# MCU.net
KiCad netlist of a schematic drawn in Altium Designer
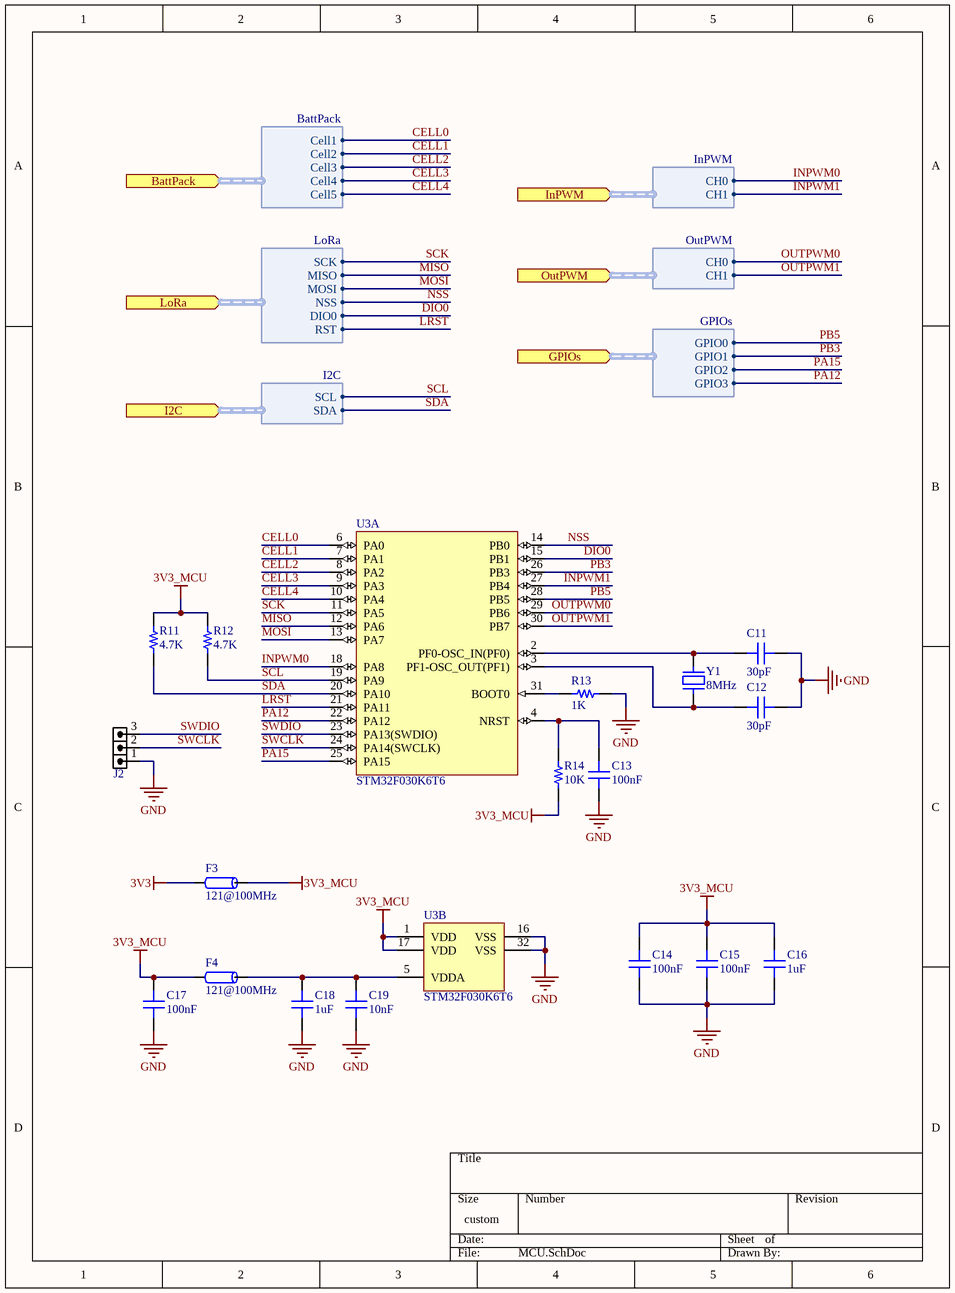
[diagram p0: MCU.SchDoc]

(export (version "E")
  (design (tool "Eeschema 10.0.6"))
  (components
    (comp (ref "C11")
      (value "30pF")
      (footprint "CAP 0603_1608")
      (description "SMT Capacitor")
      (libsource (lib "Capacitor") (part "Cap 0603"))
    )
    (comp (ref "C12")
      (value "30pF")
      (footprint "CAP 0603_1608")
      (description "SMT Capacitor")
      (libsource (lib "Capacitor") (part "Cap 0603"))
    )
    (comp (ref "C13")
      (value "100nF")
      (footprint "CAP 0603_1608")
      (description "SMT Capacitor")
      (libsource (lib "Capacitor") (part "Cap 0603"))
    )
    (comp (ref "C14")
      (value "100nF")
      (footprint "CAP 0603_1608")
      (description "SMT Capacitor")
      (libsource (lib "Capacitor") (part "Cap 0603"))
    )
    (comp (ref "C15")
      (value "100nF")
      (footprint "CAP 0603_1608")
      (description "SMT Capacitor")
      (libsource (lib "Capacitor") (part "Cap 0603"))
    )
    (comp (ref "C16")
      (value "1uF")
      (footprint "CAP 0603_1608")
      (description "SMT Capacitor")
      (libsource (lib "Capacitor") (part "Cap 0603"))
    )
    (comp (ref "C17")
      (value "100nF")
      (footprint "CAP 0603_1608")
      (description "SMT Capacitor")
      (libsource (lib "Capacitor") (part "Cap 0603"))
    )
    (comp (ref "C18")
      (value "1uF")
      (footprint "CAP 0603_1608")
      (description "SMT Capacitor")
      (libsource (lib "Capacitor") (part "Cap 0603"))
    )
    (comp (ref "C19")
      (value "10nF")
      (footprint "CAP 0603_1608")
      (description "SMT Capacitor")
      (libsource (lib "Capacitor") (part "Cap 0603"))
    )
    (comp (ref "F3")
      (value "121@100MHz")
      (footprint "Ferrite-0805")
      (description "Ferrite Bead")
      (libsource (lib "Salman_lib") (part "Ferrite Bead"))
    )
    (comp (ref "F4")
      (value "121@100MHz")
      (footprint "Ferrite-0805")
      (description "Ferrite Bead")
      (libsource (lib "Salman_lib") (part "Ferrite Bead"))
    )
    (comp (ref "J2")
      (value "HDRM3")
      (footprint "HDR_M_1X3")
      (description "CONN, HEADER, Male, pitch: 2.54mm, 3POS")
      (libsource (lib "Conn Header") (part "HDR_M_1X3"))
    )
    (comp (ref "R11")
      (value "4.7K")
      (footprint "RES 0603_1608")
      (description "SMT Resistor")
      (libsource (lib "Resistor") (part "Res 0603"))
    )
    (comp (ref "R12")
      (value "4.7K")
      (footprint "RES 0603_1608")
      (description "SMT Resistor")
      (libsource (lib "Resistor") (part "Res 0603"))
    )
    (comp (ref "R13")
      (value "1K")
      (footprint "RES 0603_1608")
      (description "SMT Resistor")
      (libsource (lib "Resistor") (part "Res 0603"))
    )
    (comp (ref "R14")
      (value "10K")
      (footprint "RES 0603_1608")
      (description "SMT Resistor")
      (libsource (lib "Resistor") (part "Res 0603"))
    )
    (comp (ref "U3")
      (value "STM32F030K6T6")
      (footprint "LQFP-32 7X7MM P0.8MM")
      (libsource (lib "Mcu") (part "STM32F030K6T6"))
    )
    (comp (ref "Y1")
      (value "8MHz")
      (footprint "HC-49S SMD")
      (description "SMT Crystal")
      (fields (field (name "PARTNUMBER") "ABLS-8.000MHZ-K4T"))
      (libsource (lib "Xtal") (part "Crystal HC-49S SMD 8MHz"))
    )
  )
  (nets
    (net (code "7") (name "/CELL0") (class "Default")
      (node (ref "U3") (pin "6") (pinfunction "PA0_6") (pintype "bidirectional"))
    )
    (net (code "8") (name "/CELL1") (class "Default")
      (node (ref "U3") (pin "7") (pinfunction "PA1_7") (pintype "bidirectional"))
    )
    (net (code "9") (name "/CELL2") (class "Default")
      (node (ref "U3") (pin "8") (pinfunction "PA2_8") (pintype "bidirectional"))
    )
    (net (code "10") (name "/CELL3") (class "Default")
      (node (ref "U3") (pin "9") (pinfunction "PA3_9") (pintype "bidirectional"))
    )
    (net (code "11") (name "/CELL4") (class "Default")
      (node (ref "U3") (pin "10") (pinfunction "PA4_10") (pintype "bidirectional"))
    )
    (net (code "12") (name "/DIO0") (class "Default")
      (node (ref "U3") (pin "15") (pinfunction "PB1_15") (pintype "bidirectional"))
    )
    (net (code "13") (name "/INPWM0") (class "Default")
      (node (ref "U3") (pin "18") (pinfunction "PA8_18") (pintype "bidirectional"))
    )
    (net (code "14") (name "/INPWM1") (class "Default")
      (node (ref "U3") (pin "27") (pinfunction "PB4_27") (pintype "bidirectional"))
    )
    (net (code "15") (name "/LRST") (class "Default")
      (node (ref "U3") (pin "21") (pinfunction "PA11_21") (pintype "bidirectional"))
    )
    (net (code "16") (name "/MISO") (class "Default")
      (node (ref "U3") (pin "12") (pinfunction "PA6_12") (pintype "bidirectional"))
    )
    (net (code "17") (name "/MOSI") (class "Default")
      (node (ref "U3") (pin "13") (pinfunction "PA7_13") (pintype "bidirectional"))
    )
    (net (code "18") (name "/NSS") (class "Default")
      (node (ref "U3") (pin "14") (pinfunction "PB0_14") (pintype "bidirectional"))
    )
    (net (code "19") (name "/OUTPWM0") (class "Default")
      (node (ref "U3") (pin "29") (pinfunction "PB6_29") (pintype "bidirectional"))
    )
    (net (code "20") (name "/OUTPWM1") (class "Default")
      (node (ref "U3") (pin "30") (pinfunction "PB7_30") (pintype "bidirectional"))
    )
    (net (code "21") (name "/PA12") (class "Default")
      (node (ref "U3") (pin "22") (pinfunction "PA12_22") (pintype "bidirectional"))
    )
    (net (code "22") (name "/PA15") (class "Default")
      (node (ref "U3") (pin "25") (pinfunction "PA15_25") (pintype "bidirectional"))
    )
    (net (code "23") (name "/PB3") (class "Default")
      (node (ref "U3") (pin "26") (pinfunction "PB3_26") (pintype "bidirectional"))
    )
    (net (code "24") (name "/PB5") (class "Default")
      (node (ref "U3") (pin "28") (pinfunction "PB5_28") (pintype "bidirectional"))
    )
    (net (code "25") (name "/SCK") (class "Default")
      (node (ref "U3") (pin "11") (pinfunction "PA5_11") (pintype "bidirectional"))
    )
    (net (code "26") (name "/SCL") (class "Default")
      (node (ref "R12") (pin "1") (pinfunction "1_1") (pintype "passive"))
      (node (ref "U3") (pin "19") (pinfunction "PA9_19") (pintype "bidirectional"))
    )
    (net (code "27") (name "/SDA") (class "Default")
      (node (ref "R11") (pin "1") (pinfunction "1_1") (pintype "passive"))
      (node (ref "U3") (pin "20") (pinfunction "PA10_20") (pintype "bidirectional"))
    )
    (net (code "28") (name "/SWCLK") (class "Default")
      (node (ref "J2") (pin "2") (pinfunction "2_2") (pintype "passive"))
      (node (ref "U3") (pin "24") (pinfunction "PA14(SWCLK)_24") (pintype "bidirectional"))
    )
    (net (code "29") (name "/SWDIO") (class "Default")
      (node (ref "J2") (pin "3") (pinfunction "3_3") (pintype "passive"))
      (node (ref "U3") (pin "23") (pinfunction "PA13(SWDIO)_23") (pintype "bidirectional"))
    )
    (net (code "36") (name "3V3") (class "Default")
      (node (ref "F3") (pin "1") (pinfunction "67_1") (pintype "passive"))
    )
    (net (code "37") (name "3V3_MCU") (class "Default")
      (node (ref "C14") (pin "2") (pinfunction "2_2") (pintype "passive"))
      (node (ref "C15") (pin "2") (pinfunction "2_2") (pintype "passive"))
      (node (ref "C16") (pin "2") (pinfunction "2_2") (pintype "passive"))
      (node (ref "C17") (pin "2") (pinfunction "2_2") (pintype "passive"))
      (node (ref "F3") (pin "2") (pinfunction "66_2") (pintype "passive"))
      (node (ref "F4") (pin "1") (pinfunction "67_1") (pintype "passive"))
      (node (ref "R11") (pin "2") (pinfunction "2_2") (pintype "passive"))
      (node (ref "R12") (pin "2") (pinfunction "2_2") (pintype "passive"))
      (node (ref "R14") (pin "1") (pinfunction "1_1") (pintype "passive"))
      (node (ref "U3") (pin "1") (pinfunction "VDD_1") (pintype "power_in"))
      (node (ref "U3") (pin "17") (pinfunction "VDD_17") (pintype "power_in"))
    )
    (net (code "38") (name "GND") (class "Default")
      (node (ref "C11") (pin "2") (pinfunction "2_2") (pintype "passive"))
      (node (ref "C12") (pin "2") (pinfunction "2_2") (pintype "passive"))
      (node (ref "C13") (pin "1") (pinfunction "1_1") (pintype "passive"))
      (node (ref "C14") (pin "1") (pinfunction "1_1") (pintype "passive"))
      (node (ref "C15") (pin "1") (pinfunction "1_1") (pintype "passive"))
      (node (ref "C16") (pin "1") (pinfunction "1_1") (pintype "passive"))
      (node (ref "C17") (pin "1") (pinfunction "1_1") (pintype "passive"))
      (node (ref "C18") (pin "1") (pinfunction "1_1") (pintype "passive"))
      (node (ref "C19") (pin "1") (pinfunction "1_1") (pintype "passive"))
      (node (ref "J2") (pin "1") (pinfunction "1_1") (pintype "passive"))
      (node (ref "R13") (pin "2") (pinfunction "2_2") (pintype "passive"))
      (node (ref "U3") (pin "16") (pinfunction "VSS_16") (pintype "power_in"))
      (node (ref "U3") (pin "32") (pinfunction "VSS_32") (pintype "power_in"))
    )
    (net (code "39") (name "Net-(F4-66)") (class "Default")
      (node (ref "C18") (pin "2") (pinfunction "2_2") (pintype "passive"))
      (node (ref "C19") (pin "2") (pinfunction "2_2") (pintype "passive"))
      (node (ref "F4") (pin "2") (pinfunction "66_2") (pintype "passive"))
      (node (ref "U3") (pin "5") (pinfunction "VDDA_5") (pintype "power_in"))
    )
    (net (code "40") (name "Net-(U3A-BOOT0)") (class "Default")
      (node (ref "R13") (pin "1") (pinfunction "1_1") (pintype "passive"))
      (node (ref "U3") (pin "31") (pinfunction "BOOT0_31") (pintype "input"))
    )
    (net (code "41") (name "Net-(U3A-NRST)") (class "Default")
      (node (ref "C13") (pin "2") (pinfunction "2_2") (pintype "passive"))
      (node (ref "R14") (pin "2") (pinfunction "2_2") (pintype "passive"))
      (node (ref "U3") (pin "4") (pinfunction "NRST_4") (pintype "bidirectional"))
    )
    (net (code "42") (name "Net-(U3A-PF0-OSC_IN(PF0))") (class "Default")
      (node (ref "C11") (pin "1") (pinfunction "1_1") (pintype "passive"))
      (node (ref "U3") (pin "2") (pinfunction "PF0-OSC_IN(PF0)_2") (pintype "bidirectional"))
      (node (ref "Y1") (pin "2") (pinfunction "2_2") (pintype "passive"))
    )
    (net (code "43") (name "Net-(U3A-PF1-OSC_OUT(PF1))") (class "Default")
      (node (ref "C12") (pin "1") (pinfunction "1_1") (pintype "passive"))
      (node (ref "U3") (pin "3") (pinfunction "PF1-OSC_OUT(PF1)_3") (pintype "bidirectional"))
      (node (ref "Y1") (pin "1") (pinfunction "1_1") (pintype "passive"))
    )
  )
)
